# Efuse.net
KiCad netlist of a schematic drawn in Altium Designer
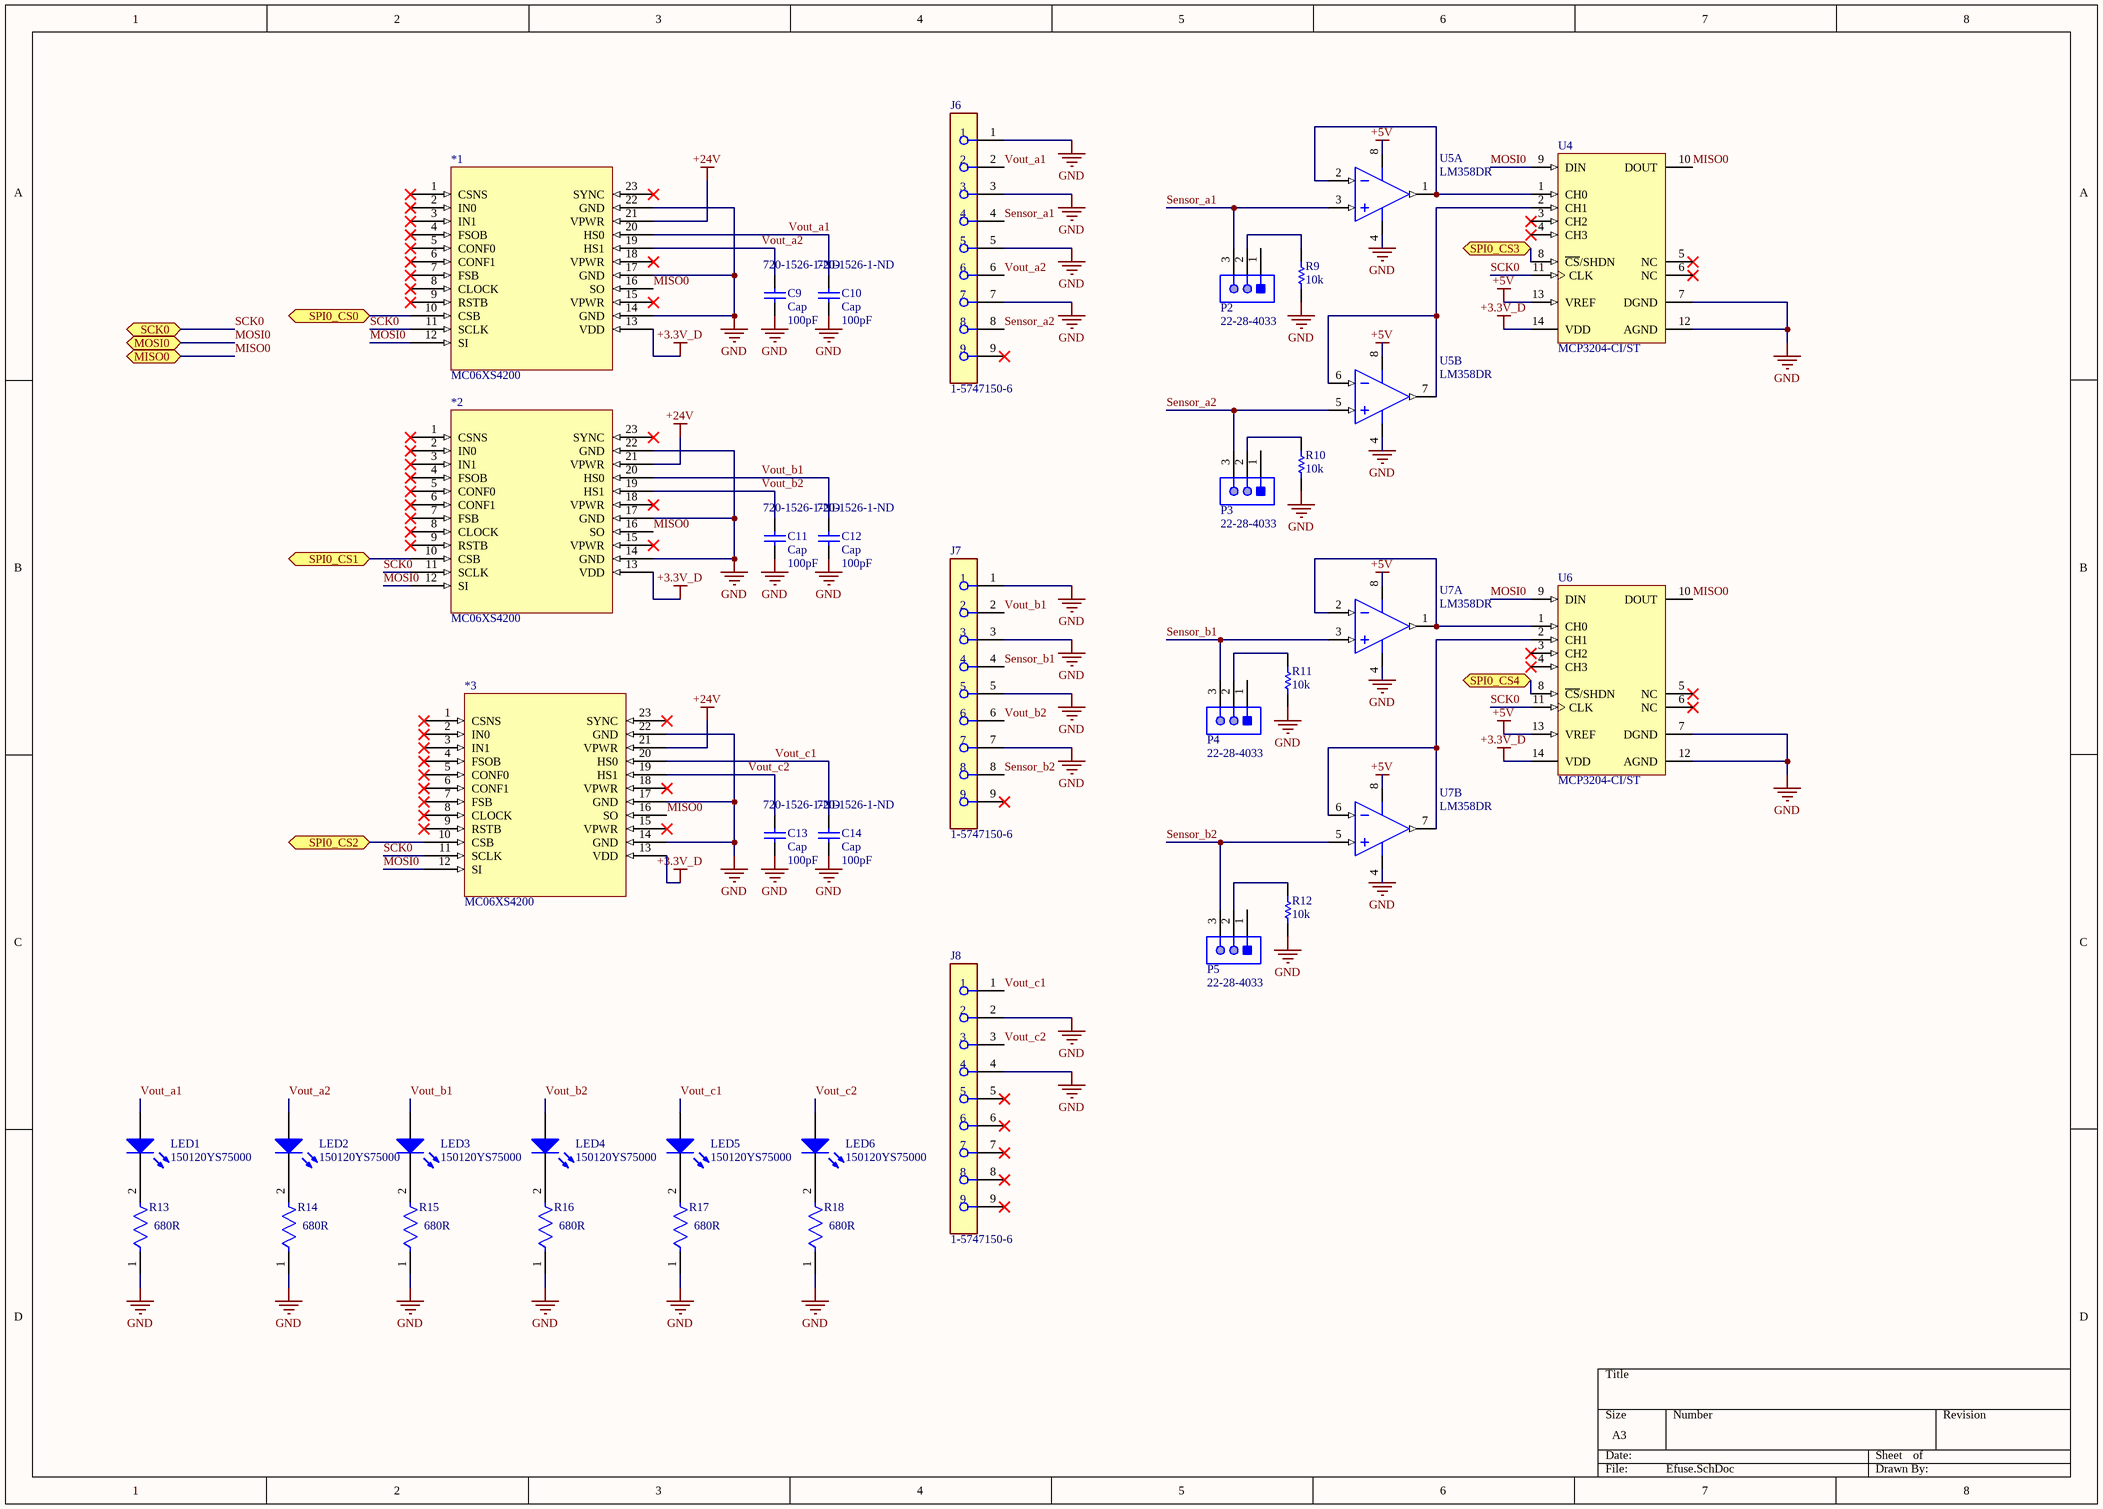
[diagram p0: Efuse.SchDoc]

(export (version "E")
  (design (tool "Eeschema 10.0.6"))
  (components
    (comp (ref "*1")
      (value "MC06XS4200")
      (footprint "MC06XS4200:PQFN50P1200X1200X220_HS-33N")
      (libsource (lib "MC06XS4200") (part "MC06XS4200"))
    )
    (comp (ref "*2")
      (value "MC06XS4200")
      (footprint "MC06XS4200:PQFN50P1200X1200X220_HS-33N")
      (libsource (lib "MC06XS4200") (part "MC06XS4200"))
    )
    (comp (ref "*3")
      (value "MC06XS4200")
      (footprint "MC06XS4200:PQFN50P1200X1200X220_HS-33N")
      (libsource (lib "MC06XS4200") (part "MC06XS4200"))
    )
    (comp (ref "C9")
      (value "Cap")
      (footprint "CAPC1608X95X40LL15T15")
      (description "MULTICOMP - MC0603F223Z500CT - KONDENSATOR, 0.022µF, 50V, Y5V, 0603")
      (fields
        (field (name "ALTIUM_VALUE") "100pF")
        (field (name "MANUFACTURER") "Multicomp")
        (field (name "MANUFACTURER PART NUMBER") "MC0603F223Z500CT")
        (field (name "SUPPLIER PART NUMBER 1") "720-1526-1-ND")
        (field (name "PUBLISHER") "Altium Limited")
      )
      (libsource (lib "Miscellaneous Devices") (part "Cap"))
    )
    (comp (ref "C10")
      (value "Cap")
      (footprint "CAPC1608X95X40LL15T15")
      (description "MULTICOMP - MC0603F223Z500CT - KONDENSATOR, 0.022µF, 50V, Y5V, 0603")
      (fields
        (field (name "ALTIUM_VALUE") "100pF")
        (field (name "MANUFACTURER") "Multicomp")
        (field (name "MANUFACTURER PART NUMBER") "MC0603F223Z500CT")
        (field (name "SUPPLIER PART NUMBER 1") "720-1526-1-ND")
        (field (name "PUBLISHER") "Altium Limited")
      )
      (libsource (lib "Miscellaneous Devices") (part "Cap"))
    )
    (comp (ref "C11")
      (value "Cap")
      (footprint "CAPC1608X95X40LL15T15")
      (description "MULTICOMP - MC0603F223Z500CT - KONDENSATOR, 0.022µF, 50V, Y5V, 0603")
      (fields
        (field (name "ALTIUM_VALUE") "100pF")
        (field (name "MANUFACTURER") "Multicomp")
        (field (name "MANUFACTURER PART NUMBER") "MC0603F223Z500CT")
        (field (name "SUPPLIER PART NUMBER 1") "720-1526-1-ND")
        (field (name "PUBLISHER") "Altium Limited")
      )
      (libsource (lib "Miscellaneous Devices") (part "Cap"))
    )
    (comp (ref "C12")
      (value "Cap")
      (footprint "CAPC1608X95X40LL15T15")
      (description "MULTICOMP - MC0603F223Z500CT - KONDENSATOR, 0.022µF, 50V, Y5V, 0603")
      (fields
        (field (name "ALTIUM_VALUE") "100pF")
        (field (name "MANUFACTURER") "Multicomp")
        (field (name "MANUFACTURER PART NUMBER") "MC0603F223Z500CT")
        (field (name "SUPPLIER PART NUMBER 1") "720-1526-1-ND")
        (field (name "PUBLISHER") "Altium Limited")
      )
      (libsource (lib "Miscellaneous Devices") (part "Cap"))
    )
    (comp (ref "C13")
      (value "Cap")
      (footprint "CAPC1608X95X40LL15T15")
      (description "MULTICOMP - MC0603F223Z500CT - KONDENSATOR, 0.022µF, 50V, Y5V, 0603")
      (fields
        (field (name "ALTIUM_VALUE") "100pF")
        (field (name "MANUFACTURER") "Multicomp")
        (field (name "MANUFACTURER PART NUMBER") "MC0603F223Z500CT")
        (field (name "SUPPLIER PART NUMBER 1") "720-1526-1-ND")
        (field (name "PUBLISHER") "Altium Limited")
      )
      (libsource (lib "Miscellaneous Devices") (part "Cap"))
    )
    (comp (ref "C14")
      (value "Cap")
      (footprint "CAPC1608X95X40LL15T15")
      (description "MULTICOMP - MC0603F223Z500CT - KONDENSATOR, 0.022µF, 50V, Y5V, 0603")
      (fields
        (field (name "ALTIUM_VALUE") "100pF")
        (field (name "MANUFACTURER") "Multicomp")
        (field (name "MANUFACTURER PART NUMBER") "MC0603F223Z500CT")
        (field (name "SUPPLIER PART NUMBER 1") "720-1526-1-ND")
        (field (name "PUBLISHER") "Altium Limited")
      )
      (libsource (lib "Miscellaneous Devices") (part "Cap"))
    )
    (comp (ref "J6")
      (value "1-5747150-6")
      (footprint "FP-1-5747150-6-MFG")
      (description "CONN D-SUB RCPT 9POS VERT SOLDER")
      (fields
        (field (name "OCTOPART") "https://octopart.com/1-5747150-6-te+connectivity-39500344")
        (field (name "MANUFACTURER") "TE Connectivity")
      )
      (libsource (lib "Altium Content Vault") (part "deee9d0d87fff07c08bdfa5b86cd5a5"))
    )
    (comp (ref "J7")
      (value "1-5747150-6")
      (footprint "FP-1-5747150-6-MFG")
      (description "CONN D-SUB RCPT 9POS VERT SOLDER")
      (fields
        (field (name "OCTOPART") "https://octopart.com/1-5747150-6-te+connectivity-39500344")
        (field (name "MANUFACTURER") "TE Connectivity")
      )
      (libsource (lib "Altium Content Vault") (part "deee9d0d87fff07c08bdfa5b86cd5a5"))
    )
    (comp (ref "J8")
      (value "1-5747150-6")
      (footprint "FP-1-5747150-6-MFG")
      (description "CONN D-SUB RCPT 9POS VERT SOLDER")
      (fields
        (field (name "OCTOPART") "https://octopart.com/1-5747150-6-te+connectivity-39500344")
        (field (name "MANUFACTURER") "TE Connectivity")
      )
      (libsource (lib "Altium Content Vault") (part "deee9d0d87fff07c08bdfa5b86cd5a5"))
    )
    (comp (ref "LED1")
      (value "150120YS75000")
      (footprint "1206_A")
      (description "SMD mono-color Chip LED, WL-SMCW, Yellow")
      (fields (field (name "MANUFACTURER") "Wuerth Elektronik"))
      (libsource (lib "Altium Content Vault") (part "WE-LED_K1A2-2"))
    )
    (comp (ref "LED2")
      (value "150120YS75000")
      (footprint "1206_A")
      (description "SMD mono-color Chip LED, WL-SMCW, Yellow")
      (fields (field (name "MANUFACTURER") "Wuerth Elektronik"))
      (libsource (lib "Altium Content Vault") (part "WE-LED_K1A2-2"))
    )
    (comp (ref "LED3")
      (value "150120YS75000")
      (footprint "1206_A")
      (description "SMD mono-color Chip LED, WL-SMCW, Yellow")
      (fields (field (name "MANUFACTURER") "Wuerth Elektronik"))
      (libsource (lib "Altium Content Vault") (part "WE-LED_K1A2-2"))
    )
    (comp (ref "LED4")
      (value "150120YS75000")
      (footprint "1206_A")
      (description "SMD mono-color Chip LED, WL-SMCW, Yellow")
      (fields (field (name "MANUFACTURER") "Wuerth Elektronik"))
      (libsource (lib "Altium Content Vault") (part "WE-LED_K1A2-2"))
    )
    (comp (ref "LED5")
      (value "150120YS75000")
      (footprint "1206_A")
      (description "SMD mono-color Chip LED, WL-SMCW, Yellow")
      (fields (field (name "MANUFACTURER") "Wuerth Elektronik"))
      (libsource (lib "Altium Content Vault") (part "WE-LED_K1A2-2"))
    )
    (comp (ref "LED6")
      (value "150120YS75000")
      (footprint "1206_A")
      (description "SMD mono-color Chip LED, WL-SMCW, Yellow")
      (fields (field (name "MANUFACTURER") "Wuerth Elektronik"))
      (libsource (lib "Altium Content Vault") (part "WE-LED_K1A2-2"))
    )
    (comp (ref "P2")
      (value "22-28-4033")
      (footprint "MOLX-22-28-4033_V")
      (description "Male Header, Pitch 2.54 mm, 1 x 3 Position, Height 8.38 mm, Tail Length 3.18 mm, RoHS, Bulk")
      (fields (field (name "MANUFACTURER") "Molex"))
      (libsource (lib "Altium Content Vault") (part "CN-1P-M-R3"))
    )
    (comp (ref "P3")
      (value "22-28-4033")
      (footprint "MOLX-22-28-4033_V")
      (description "Male Header, Pitch 2.54 mm, 1 x 3 Position, Height 8.38 mm, Tail Length 3.18 mm, RoHS, Bulk")
      (fields (field (name "MANUFACTURER") "Molex"))
      (libsource (lib "Altium Content Vault") (part "CN-1P-M-R3"))
    )
    (comp (ref "P4")
      (value "22-28-4033")
      (footprint "MOLX-22-28-4033_V")
      (description "Male Header, Pitch 2.54 mm, 1 x 3 Position, Height 8.38 mm, Tail Length 3.18 mm, RoHS, Bulk")
      (fields (field (name "MANUFACTURER") "Molex"))
      (libsource (lib "Altium Content Vault") (part "CN-1P-M-R3"))
    )
    (comp (ref "P5")
      (value "22-28-4033")
      (footprint "MOLX-22-28-4033_V")
      (description "Male Header, Pitch 2.54 mm, 1 x 3 Position, Height 8.38 mm, Tail Length 3.18 mm, RoHS, Bulk")
      (fields (field (name "MANUFACTURER") "Molex"))
      (libsource (lib "Altium Content Vault") (part "CN-1P-M-R3"))
    )
    (comp (ref "R9")
      (value "10k")
      (footprint "RESC1005X40X25NL05T05")
      (fields (field (name "PART NUMBER") "ERT-J0ER103J") (field (name "MANUFACTURER") "Panasonic"))
      (libsource (lib "Altium Content Vault") (part "RES"))
    )
    (comp (ref "R10")
      (value "10k")
      (footprint "RESC1005X40X25NL05T05")
      (fields (field (name "PART NUMBER") "ERT-J0ER103J") (field (name "MANUFACTURER") "Panasonic"))
      (libsource (lib "Altium Content Vault") (part "RES"))
    )
    (comp (ref "R11")
      (value "10k")
      (footprint "RESC1005X40X25NL05T05")
      (fields (field (name "PART NUMBER") "ERT-J0ER103J") (field (name "MANUFACTURER") "Panasonic"))
      (libsource (lib "Altium Content Vault") (part "RES"))
    )
    (comp (ref "R12")
      (value "10k")
      (footprint "RESC1005X40X25NL05T05")
      (fields (field (name "PART NUMBER") "ERT-J0ER103J") (field (name "MANUFACTURER") "Panasonic"))
      (libsource (lib "Altium Content Vault") (part "RES"))
    )
    (comp (ref "R13")
      (value "CRCW0603680RFKEA")
      (footprint "FP-CRCW0603-e3-MFG")
      (description "RES Thick Film, 680Ω, 1%, 0.1W, 100ppm/°C, 0603")
      (fields (field (name "TOLERANCE") "1%") (field (name "RESISTANCE") "680R"))
      (libsource (lib "Altium Content Vault") (part "1029c3af85768c4190bb7ad29bc67b5"))
    )
    (comp (ref "R14")
      (value "CRCW0603680RFKEA")
      (footprint "FP-CRCW0603-e3-MFG")
      (description "RES Thick Film, 680Ω, 1%, 0.1W, 100ppm/°C, 0603")
      (fields (field (name "TOLERANCE") "1%") (field (name "RESISTANCE") "680R"))
      (libsource (lib "Altium Content Vault") (part "1029c3af85768c4190bb7ad29bc67b5"))
    )
    (comp (ref "R15")
      (value "CRCW0603680RFKEA")
      (footprint "FP-CRCW0603-e3-MFG")
      (description "RES Thick Film, 680Ω, 1%, 0.1W, 100ppm/°C, 0603")
      (fields (field (name "TOLERANCE") "1%") (field (name "RESISTANCE") "680R"))
      (libsource (lib "Altium Content Vault") (part "1029c3af85768c4190bb7ad29bc67b5"))
    )
    (comp (ref "R16")
      (value "CRCW0603680RFKEA")
      (footprint "FP-CRCW0603-e3-MFG")
      (description "RES Thick Film, 680Ω, 1%, 0.1W, 100ppm/°C, 0603")
      (fields (field (name "TOLERANCE") "1%") (field (name "RESISTANCE") "680R"))
      (libsource (lib "Altium Content Vault") (part "1029c3af85768c4190bb7ad29bc67b5"))
    )
    (comp (ref "R17")
      (value "CRCW0603680RFKEA")
      (footprint "FP-CRCW0603-e3-MFG")
      (description "RES Thick Film, 680Ω, 1%, 0.1W, 100ppm/°C, 0603")
      (fields (field (name "TOLERANCE") "1%") (field (name "RESISTANCE") "680R"))
      (libsource (lib "Altium Content Vault") (part "1029c3af85768c4190bb7ad29bc67b5"))
    )
    (comp (ref "R18")
      (value "CRCW0603680RFKEA")
      (footprint "FP-CRCW0603-e3-MFG")
      (description "RES Thick Film, 680Ω, 1%, 0.1W, 100ppm/°C, 0603")
      (fields (field (name "TOLERANCE") "1%") (field (name "RESISTANCE") "680R"))
      (libsource (lib "Altium Content Vault") (part "1029c3af85768c4190bb7ad29bc67b5"))
    )
    (comp (ref "U4")
      (value "MCP3204-CI/ST")
      (footprint "TSSOP-ST14_N")
      (libsource (lib "Altium Content Vault") (part "CON-ADC-MCP3004-14"))
    )
    (comp (ref "U5")
      (value "LM358DR")
      (footprint "D0008A_L")
      (libsource (lib "Altium Content Vault") (part "TI-LM358-8"))
    )
    (comp (ref "U6")
      (value "MCP3204-CI/ST")
      (footprint "TSSOP-ST14_N")
      (libsource (lib "Altium Content Vault") (part "CON-ADC-MCP3004-14"))
    )
    (comp (ref "U7")
      (value "LM358DR")
      (footprint "D0008A_L")
      (libsource (lib "Altium Content Vault") (part "TI-LM358-8"))
    )
  )
  (nets
    (net (code "1") (name "+3.3V_D") (class "Default")
      (node (ref "*1") (pin "13") (pinfunction "VDD_13") (pintype "input"))
      (node (ref "*2") (pin "13") (pinfunction "VDD_13") (pintype "input"))
      (node (ref "*3") (pin "13") (pinfunction "VDD_13") (pintype "input"))
      (node (ref "U4") (pin "14") (pinfunction "VDD_14") (pintype "power_in"))
      (node (ref "U6") (pin "14") (pinfunction "VDD_14") (pintype "power_in"))
    )
    (net (code "2") (name "+5V") (class "Default")
      (node (ref "U4") (pin "13") (pinfunction "VREF_13") (pintype "input"))
      (node (ref "U5") (pin "8") (pinfunction "VCC_8") (pintype "power_in"))
      (node (ref "U6") (pin "13") (pinfunction "VREF_13") (pintype "input"))
      (node (ref "U7") (pin "8") (pinfunction "VCC_8") (pintype "power_in"))
    )
    (net (code "3") (name "+24V") (class "Default")
      (node (ref "*1") (pin "21") (pinfunction "VPWR_21") (pintype "input"))
      (node (ref "*2") (pin "21") (pinfunction "VPWR_21") (pintype "input"))
      (node (ref "*3") (pin "21") (pinfunction "VPWR_21") (pintype "input"))
    )
    (net (code "4") (name "/MISO0") (class "Default")
      (node (ref "*1") (pin "16") (pinfunction "SO_16") (pintype "input"))
      (node (ref "*2") (pin "16") (pinfunction "SO_16") (pintype "input"))
      (node (ref "*3") (pin "16") (pinfunction "SO_16") (pintype "input"))
      (node (ref "U4") (pin "10") (pinfunction "DOUT_10") (pintype "tri_state"))
      (node (ref "U6") (pin "10") (pinfunction "DOUT_10") (pintype "tri_state"))
    )
    (net (code "5") (name "/MOSI0") (class "Default")
      (node (ref "*1") (pin "12") (pinfunction "SI_12") (pintype "input"))
      (node (ref "*2") (pin "12") (pinfunction "SI_12") (pintype "input"))
      (node (ref "*3") (pin "12") (pinfunction "SI_12") (pintype "input"))
      (node (ref "U4") (pin "9") (pinfunction "DIN_9") (pintype "input"))
      (node (ref "U6") (pin "9") (pinfunction "DIN_9") (pintype "input"))
    )
    (net (code "6") (name "/SCK0") (class "Default")
      (node (ref "*1") (pin "11") (pinfunction "SCLK_11") (pintype "input"))
      (node (ref "*2") (pin "11") (pinfunction "SCLK_11") (pintype "input"))
      (node (ref "*3") (pin "11") (pinfunction "SCLK_11") (pintype "input"))
      (node (ref "U4") (pin "11") (pinfunction "CLK_11") (pintype "input"))
      (node (ref "U6") (pin "11") (pinfunction "CLK_11") (pintype "input"))
    )
    (net (code "7") (name "/SPI0_CS0") (class "Default")
      (node (ref "*1") (pin "10") (pinfunction "CSB_10") (pintype "input"))
    )
    (net (code "8") (name "/SPI0_CS1") (class "Default")
      (node (ref "*2") (pin "10") (pinfunction "CSB_10") (pintype "input"))
    )
    (net (code "9") (name "/SPI0_CS2") (class "Default")
      (node (ref "*3") (pin "10") (pinfunction "CSB_10") (pintype "input"))
    )
    (net (code "10") (name "/SPI0_CS3") (class "Default")
      (node (ref "U4") (pin "8") (pinfunction "~{CS}/SHDN_8") (pintype "input"))
    )
    (net (code "11") (name "/SPI0_CS4") (class "Default")
      (node (ref "U6") (pin "8") (pinfunction "~{CS}/SHDN_8") (pintype "input"))
    )
    (net (code "12") (name "/Sensor_a1") (class "Default")
      (node (ref "J6") (pin "4") (pinfunction "4_4") (pintype "passive"))
      (node (ref "P2") (pin "3") (pinfunction "3_3") (pintype "passive"))
      (node (ref "U5") (pin "3") (pinfunction "1IN+_3") (pintype "input"))
    )
    (net (code "13") (name "/Sensor_a2") (class "Default")
      (node (ref "J6") (pin "8") (pinfunction "8_8") (pintype "passive"))
      (node (ref "P3") (pin "3") (pinfunction "3_3") (pintype "passive"))
      (node (ref "U5") (pin "5") (pinfunction "2IN+_5") (pintype "input"))
    )
    (net (code "14") (name "/Sensor_b1") (class "Default")
      (node (ref "J7") (pin "4") (pinfunction "4_4") (pintype "passive"))
      (node (ref "P4") (pin "3") (pinfunction "3_3") (pintype "passive"))
      (node (ref "U7") (pin "3") (pinfunction "1IN+_3") (pintype "input"))
    )
    (net (code "15") (name "/Sensor_b2") (class "Default")
      (node (ref "J7") (pin "8") (pinfunction "8_8") (pintype "passive"))
      (node (ref "P5") (pin "3") (pinfunction "3_3") (pintype "passive"))
      (node (ref "U7") (pin "5") (pinfunction "2IN+_5") (pintype "input"))
    )
    (net (code "16") (name "/Vout_a1") (class "Default")
      (node (ref "*1") (pin "20") (pinfunction "HS0_20") (pintype "input"))
      (node (ref "C10") (pin "2") (pinfunction "2_2") (pintype "passive"))
      (node (ref "J6") (pin "2") (pinfunction "2_2") (pintype "passive"))
      (node (ref "LED1") (pin "2") (pinfunction "A_2") (pintype "passive"))
    )
    (net (code "17") (name "/Vout_a2") (class "Default")
      (node (ref "*1") (pin "19") (pinfunction "HS1_19") (pintype "input"))
      (node (ref "C9") (pin "2") (pinfunction "2_2") (pintype "passive"))
      (node (ref "J6") (pin "6") (pinfunction "6_6") (pintype "passive"))
      (node (ref "LED2") (pin "2") (pinfunction "A_2") (pintype "passive"))
    )
    (net (code "18") (name "/Vout_b1") (class "Default")
      (node (ref "*2") (pin "20") (pinfunction "HS0_20") (pintype "input"))
      (node (ref "C12") (pin "2") (pinfunction "2_2") (pintype "passive"))
      (node (ref "J7") (pin "2") (pinfunction "2_2") (pintype "passive"))
      (node (ref "LED3") (pin "2") (pinfunction "A_2") (pintype "passive"))
    )
    (net (code "19") (name "/Vout_b2") (class "Default")
      (node (ref "*2") (pin "19") (pinfunction "HS1_19") (pintype "input"))
      (node (ref "C11") (pin "2") (pinfunction "2_2") (pintype "passive"))
      (node (ref "J7") (pin "6") (pinfunction "6_6") (pintype "passive"))
      (node (ref "LED4") (pin "2") (pinfunction "A_2") (pintype "passive"))
    )
    (net (code "20") (name "/Vout_c1") (class "Default")
      (node (ref "*3") (pin "20") (pinfunction "HS0_20") (pintype "input"))
      (node (ref "C14") (pin "2") (pinfunction "2_2") (pintype "passive"))
      (node (ref "J8") (pin "1") (pinfunction "1_1") (pintype "passive"))
      (node (ref "LED5") (pin "2") (pinfunction "A_2") (pintype "passive"))
    )
    (net (code "21") (name "/Vout_c2") (class "Default")
      (node (ref "*3") (pin "19") (pinfunction "HS1_19") (pintype "input"))
      (node (ref "C13") (pin "2") (pinfunction "2_2") (pintype "passive"))
      (node (ref "J8") (pin "3") (pinfunction "3_3") (pintype "passive"))
      (node (ref "LED6") (pin "2") (pinfunction "A_2") (pintype "passive"))
    )
    (net (code "22") (name "GND") (class "Default")
      (node (ref "*1") (pin "14") (pinfunction "GND_14") (pintype "input"))
      (node (ref "*1") (pin "17") (pinfunction "GND_17") (pintype "input"))
      (node (ref "*1") (pin "22") (pinfunction "GND_22") (pintype "input"))
      (node (ref "*2") (pin "14") (pinfunction "GND_14") (pintype "input"))
      (node (ref "*2") (pin "17") (pinfunction "GND_17") (pintype "input"))
      (node (ref "*2") (pin "22") (pinfunction "GND_22") (pintype "input"))
      (node (ref "*3") (pin "14") (pinfunction "GND_14") (pintype "input"))
      (node (ref "*3") (pin "17") (pinfunction "GND_17") (pintype "input"))
      (node (ref "*3") (pin "22") (pinfunction "GND_22") (pintype "input"))
      (node (ref "C10") (pin "1") (pinfunction "1_1") (pintype "passive"))
      (node (ref "C11") (pin "1") (pinfunction "1_1") (pintype "passive"))
      (node (ref "C12") (pin "1") (pinfunction "1_1") (pintype "passive"))
      (node (ref "C13") (pin "1") (pinfunction "1_1") (pintype "passive"))
      (node (ref "C14") (pin "1") (pinfunction "1_1") (pintype "passive"))
      (node (ref "C9") (pin "1") (pinfunction "1_1") (pintype "passive"))
      (node (ref "J6") (pin "1") (pinfunction "1_1") (pintype "passive"))
      (node (ref "J6") (pin "3") (pinfunction "3_3") (pintype "passive"))
      (node (ref "J6") (pin "5") (pinfunction "5_5") (pintype "passive"))
      (node (ref "J6") (pin "7") (pinfunction "7_7") (pintype "passive"))
      (node (ref "J7") (pin "1") (pinfunction "1_1") (pintype "passive"))
      (node (ref "J7") (pin "3") (pinfunction "3_3") (pintype "passive"))
      (node (ref "J7") (pin "5") (pinfunction "5_5") (pintype "passive"))
      (node (ref "J7") (pin "7") (pinfunction "7_7") (pintype "passive"))
      (node (ref "J8") (pin "2") (pinfunction "2_2") (pintype "passive"))
      (node (ref "J8") (pin "4") (pinfunction "4_4") (pintype "passive"))
      (node (ref "R10") (pin "1") (pinfunction "1_1") (pintype "passive"))
      (node (ref "R11") (pin "1") (pinfunction "1_1") (pintype "passive"))
      (node (ref "R12") (pin "1") (pinfunction "1_1") (pintype "passive"))
      (node (ref "R13") (pin "1") (pinfunction "1_1") (pintype "passive"))
      (node (ref "R14") (pin "1") (pinfunction "1_1") (pintype "passive"))
      (node (ref "R15") (pin "1") (pinfunction "1_1") (pintype "passive"))
      (node (ref "R16") (pin "1") (pinfunction "1_1") (pintype "passive"))
      (node (ref "R17") (pin "1") (pinfunction "1_1") (pintype "passive"))
      (node (ref "R18") (pin "1") (pinfunction "1_1") (pintype "passive"))
      (node (ref "R9") (pin "1") (pinfunction "1_1") (pintype "passive"))
      (node (ref "U4") (pin "12") (pinfunction "AGND_12") (pintype "power_in"))
      (node (ref "U4") (pin "7") (pinfunction "DGND_7") (pintype "power_in"))
      (node (ref "U5") (pin "4") (pinfunction "GND_4") (pintype "power_in"))
      (node (ref "U6") (pin "12") (pinfunction "AGND_12") (pintype "power_in"))
      (node (ref "U6") (pin "7") (pinfunction "DGND_7") (pintype "power_in"))
      (node (ref "U7") (pin "4") (pinfunction "GND_4") (pintype "power_in"))
    )
    (net (code "23") (name "Net-(LED1-K)") (class "Default")
      (node (ref "LED1") (pin "1") (pinfunction "K_1") (pintype "passive"))
      (node (ref "R13") (pin "2") (pinfunction "2_2") (pintype "passive"))
    )
    (net (code "24") (name "Net-(LED2-K)") (class "Default")
      (node (ref "LED2") (pin "1") (pinfunction "K_1") (pintype "passive"))
      (node (ref "R14") (pin "2") (pinfunction "2_2") (pintype "passive"))
    )
    (net (code "25") (name "Net-(LED3-K)") (class "Default")
      (node (ref "LED3") (pin "1") (pinfunction "K_1") (pintype "passive"))
      (node (ref "R15") (pin "2") (pinfunction "2_2") (pintype "passive"))
    )
    (net (code "26") (name "Net-(LED4-K)") (class "Default")
      (node (ref "LED4") (pin "1") (pinfunction "K_1") (pintype "passive"))
      (node (ref "R16") (pin "2") (pinfunction "2_2") (pintype "passive"))
    )
    (net (code "27") (name "Net-(LED5-K)") (class "Default")
      (node (ref "LED5") (pin "1") (pinfunction "K_1") (pintype "passive"))
      (node (ref "R17") (pin "2") (pinfunction "2_2") (pintype "passive"))
    )
    (net (code "28") (name "Net-(LED6-K)") (class "Default")
      (node (ref "LED6") (pin "1") (pinfunction "K_1") (pintype "passive"))
      (node (ref "R18") (pin "2") (pinfunction "2_2") (pintype "passive"))
    )
    (net (code "29") (name "Net-(P2-Pad2)") (class "Default")
      (node (ref "P2") (pin "2") (pinfunction "2_2") (pintype "passive"))
      (node (ref "R9") (pin "2") (pinfunction "2_2") (pintype "passive"))
    )
    (net (code "30") (name "Net-(P3-Pad2)") (class "Default")
      (node (ref "P3") (pin "2") (pinfunction "2_2") (pintype "passive"))
      (node (ref "R10") (pin "2") (pinfunction "2_2") (pintype "passive"))
    )
    (net (code "31") (name "Net-(P4-Pad2)") (class "Default")
      (node (ref "P4") (pin "2") (pinfunction "2_2") (pintype "passive"))
      (node (ref "R11") (pin "2") (pinfunction "2_2") (pintype "passive"))
    )
    (net (code "32") (name "Net-(P5-Pad2)") (class "Default")
      (node (ref "P5") (pin "2") (pinfunction "2_2") (pintype "passive"))
      (node (ref "R12") (pin "2") (pinfunction "2_2") (pintype "passive"))
    )
    (net (code "33") (name "Net-(U4-CH0)") (class "Default")
      (node (ref "U4") (pin "1") (pinfunction "CH0_1") (pintype "input"))
      (node (ref "U5") (pin "1") (pinfunction "1OUT_1") (pintype "output"))
      (node (ref "U5") (pin "2") (pinfunction "1IN-_2") (pintype "input"))
    )
    (net (code "34") (name "Net-(U4-CH1)") (class "Default")
      (node (ref "U4") (pin "2") (pinfunction "CH1_2") (pintype "input"))
      (node (ref "U5") (pin "6") (pinfunction "2IN-_6") (pintype "input"))
      (node (ref "U5") (pin "7") (pinfunction "2OUT_7") (pintype "output"))
    )
    (net (code "35") (name "Net-(U6-CH0)") (class "Default")
      (node (ref "U6") (pin "1") (pinfunction "CH0_1") (pintype "input"))
      (node (ref "U7") (pin "1") (pinfunction "1OUT_1") (pintype "output"))
      (node (ref "U7") (pin "2") (pinfunction "1IN-_2") (pintype "input"))
    )
    (net (code "36") (name "Net-(U6-CH1)") (class "Default")
      (node (ref "U6") (pin "2") (pinfunction "CH1_2") (pintype "input"))
      (node (ref "U7") (pin "6") (pinfunction "2IN-_6") (pintype "input"))
      (node (ref "U7") (pin "7") (pinfunction "2OUT_7") (pintype "output"))
    )
    (net (code "37") (name "unconnected-(*1-CLOCK-Pad8)") (class "Default")
      (node (ref "*1") (pin "8") (pinfunction "CLOCK_8") (pintype "input+no_connect"))
    )
    (net (code "38") (name "unconnected-(*1-CONF0-Pad5)") (class "Default")
      (node (ref "*1") (pin "5") (pinfunction "CONF0_5") (pintype "input+no_connect"))
    )
    (net (code "39") (name "unconnected-(*1-CONF1-Pad6)") (class "Default")
      (node (ref "*1") (pin "6") (pinfunction "CONF1_6") (pintype "input+no_connect"))
    )
    (net (code "40") (name "unconnected-(*1-CSNS-Pad1)") (class "Default")
      (node (ref "*1") (pin "1") (pinfunction "CSNS_1") (pintype "input+no_connect"))
    )
    (net (code "41") (name "unconnected-(*1-FSB-Pad7)") (class "Default")
      (node (ref "*1") (pin "7") (pinfunction "FSB_7") (pintype "input+no_connect"))
    )
    (net (code "42") (name "unconnected-(*1-FSOB-Pad4)") (class "Default")
      (node (ref "*1") (pin "4") (pinfunction "FSOB_4") (pintype "input+no_connect"))
    )
    (net (code "43") (name "unconnected-(*1-IN0-Pad2)") (class "Default")
      (node (ref "*1") (pin "2") (pinfunction "IN0_2") (pintype "input+no_connect"))
    )
    (net (code "44") (name "unconnected-(*1-IN1-Pad3)") (class "Default")
      (node (ref "*1") (pin "3") (pinfunction "IN1_3") (pintype "input+no_connect"))
    )
    (net (code "45") (name "unconnected-(*1-RSTB-Pad9)") (class "Default")
      (node (ref "*1") (pin "9") (pinfunction "RSTB_9") (pintype "input+no_connect"))
    )
    (net (code "46") (name "unconnected-(*1-SYNC-Pad23)") (class "Default")
      (node (ref "*1") (pin "23") (pinfunction "SYNC_23") (pintype "input+no_connect"))
    )
    (net (code "47") (name "unconnected-(*1-VPWR-Pad15)") (class "Default")
      (node (ref "*1") (pin "15") (pinfunction "VPWR_15") (pintype "input+no_connect"))
    )
    (net (code "48") (name "unconnected-(*1-VPWR-Pad18)") (class "Default")
      (node (ref "*1") (pin "18") (pinfunction "VPWR_18") (pintype "input+no_connect"))
    )
    (net (code "49") (name "unconnected-(*2-CLOCK-Pad8)") (class "Default")
      (node (ref "*2") (pin "8") (pinfunction "CLOCK_8") (pintype "input+no_connect"))
    )
    (net (code "50") (name "unconnected-(*2-CONF0-Pad5)") (class "Default")
      (node (ref "*2") (pin "5") (pinfunction "CONF0_5") (pintype "input+no_connect"))
    )
    (net (code "51") (name "unconnected-(*2-CONF1-Pad6)") (class "Default")
      (node (ref "*2") (pin "6") (pinfunction "CONF1_6") (pintype "input+no_connect"))
    )
    (net (code "52") (name "unconnected-(*2-CSNS-Pad1)") (class "Default")
      (node (ref "*2") (pin "1") (pinfunction "CSNS_1") (pintype "input+no_connect"))
    )
    (net (code "53") (name "unconnected-(*2-FSB-Pad7)") (class "Default")
      (node (ref "*2") (pin "7") (pinfunction "FSB_7") (pintype "input+no_connect"))
    )
    (net (code "54") (name "unconnected-(*2-FSOB-Pad4)") (class "Default")
      (node (ref "*2") (pin "4") (pinfunction "FSOB_4") (pintype "input+no_connect"))
    )
    (net (code "55") (name "unconnected-(*2-IN0-Pad2)") (class "Default")
      (node (ref "*2") (pin "2") (pinfunction "IN0_2") (pintype "input+no_connect"))
    )
    (net (code "56") (name "unconnected-(*2-IN1-Pad3)") (class "Default")
      (node (ref "*2") (pin "3") (pinfunction "IN1_3") (pintype "input+no_connect"))
    )
    (net (code "57") (name "unconnected-(*2-RSTB-Pad9)") (class "Default")
      (node (ref "*2") (pin "9") (pinfunction "RSTB_9") (pintype "input+no_connect"))
    )
    (net (code "58") (name "unconnected-(*2-SYNC-Pad23)") (class "Default")
      (node (ref "*2") (pin "23") (pinfunction "SYNC_23") (pintype "input+no_connect"))
    )
    (net (code "59") (name "unconnected-(*2-VPWR-Pad15)") (class "Default")
      (node (ref "*2") (pin "15") (pinfunction "VPWR_15") (pintype "input+no_connect"))
    )
    (net (code "60") (name "unconnected-(*2-VPWR-Pad18)") (class "Default")
      (node (ref "*2") (pin "18") (pinfunction "VPWR_18") (pintype "input+no_connect"))
    )
    (net (code "61") (name "unconnected-(*3-CLOCK-Pad8)") (class "Default")
      (node (ref "*3") (pin "8") (pinfunction "CLOCK_8") (pintype "input+no_connect"))
    )
    (net (code "62") (name "unconnected-(*3-CONF0-Pad5)") (class "Default")
      (node (ref "*3") (pin "5") (pinfunction "CONF0_5") (pintype "input+no_connect"))
    )
    (net (code "63") (name "unconnected-(*3-CONF1-Pad6)") (class "Default")
      (node (ref "*3") (pin "6") (pinfunction "CONF1_6") (pintype "input+no_connect"))
    )
    (net (code "64") (name "unconnected-(*3-CSNS-Pad1)") (class "Default")
      (node (ref "*3") (pin "1") (pinfunction "CSNS_1") (pintype "input+no_connect"))
    )
    (net (code "65") (name "unconnected-(*3-FSB-Pad7)") (class "Default")
      (node (ref "*3") (pin "7") (pinfunction "FSB_7") (pintype "input+no_connect"))
    )
    (net (code "66") (name "unconnected-(*3-FSOB-Pad4)") (class "Default")
      (node (ref "*3") (pin "4") (pinfunction "FSOB_4") (pintype "input+no_connect"))
    )
    (net (code "67") (name "unconnected-(*3-IN0-Pad2)") (class "Default")
      (node (ref "*3") (pin "2") (pinfunction "IN0_2") (pintype "input+no_connect"))
    )
    (net (code "68") (name "unconnected-(*3-IN1-Pad3)") (class "Default")
      (node (ref "*3") (pin "3") (pinfunction "IN1_3") (pintype "input+no_connect"))
    )
    (net (code "69") (name "unconnected-(*3-RSTB-Pad9)") (class "Default")
      (node (ref "*3") (pin "9") (pinfunction "RSTB_9") (pintype "input+no_connect"))
    )
    (net (code "70") (name "unconnected-(*3-SYNC-Pad23)") (class "Default")
      (node (ref "*3") (pin "23") (pinfunction "SYNC_23") (pintype "input+no_connect"))
    )
    (net (code "71") (name "unconnected-(*3-VPWR-Pad15)") (class "Default")
      (node (ref "*3") (pin "15") (pinfunction "VPWR_15") (pintype "input+no_connect"))
    )
    (net (code "72") (name "unconnected-(*3-VPWR-Pad18)") (class "Default")
      (node (ref "*3") (pin "18") (pinfunction "VPWR_18") (pintype "input+no_connect"))
    )
    (net (code "73") (name "unconnected-(J6-Pad9)") (class "Default")
      (node (ref "J6") (pin "9") (pinfunction "9_9") (pintype "passive+no_connect"))
    )
    (net (code "74") (name "unconnected-(J7-Pad9)") (class "Default")
      (node (ref "J7") (pin "9") (pinfunction "9_9") (pintype "passive+no_connect"))
    )
    (net (code "75") (name "unconnected-(J8-Pad5)") (class "Default")
      (node (ref "J8") (pin "5") (pinfunction "5_5") (pintype "passive+no_connect"))
    )
    (net (code "76") (name "unconnected-(J8-Pad6)") (class "Default")
      (node (ref "J8") (pin "6") (pinfunction "6_6") (pintype "passive+no_connect"))
    )
    (net (code "77") (name "unconnected-(J8-Pad7)") (class "Default")
      (node (ref "J8") (pin "7") (pinfunction "7_7") (pintype "passive+no_connect"))
    )
    (net (code "78") (name "unconnected-(J8-Pad8)") (class "Default")
      (node (ref "J8") (pin "8") (pinfunction "8_8") (pintype "passive+no_connect"))
    )
    (net (code "79") (name "unconnected-(J8-Pad9)") (class "Default")
      (node (ref "J8") (pin "9") (pinfunction "9_9") (pintype "passive+no_connect"))
    )
    (net (code "80") (name "unconnected-(P2-Pad1)") (class "Default")
      (node (ref "P2") (pin "1") (pinfunction "1_1") (pintype "passive"))
    )
    (net (code "81") (name "unconnected-(P3-Pad1)") (class "Default")
      (node (ref "P3") (pin "1") (pinfunction "1_1") (pintype "passive"))
    )
    (net (code "82") (name "unconnected-(P4-Pad1)") (class "Default")
      (node (ref "P4") (pin "1") (pinfunction "1_1") (pintype "passive"))
    )
    (net (code "83") (name "unconnected-(P5-Pad1)") (class "Default")
      (node (ref "P5") (pin "1") (pinfunction "1_1") (pintype "passive"))
    )
    (net (code "84") (name "unconnected-(U4-CH2-Pad3)") (class "Default")
      (node (ref "U4") (pin "3") (pinfunction "CH2_3") (pintype "input+no_connect"))
    )
    (net (code "85") (name "unconnected-(U4-CH3-Pad4)") (class "Default")
      (node (ref "U4") (pin "4") (pinfunction "CH3_4") (pintype "input+no_connect"))
    )
    (net (code "86") (name "unconnected-(U4-NC-Pad5)") (class "Default")
      (node (ref "U4") (pin "5") (pinfunction "NC_5") (pintype "passive+no_connect"))
    )
    (net (code "87") (name "unconnected-(U4-NC-Pad6)") (class "Default")
      (node (ref "U4") (pin "6") (pinfunction "NC_6") (pintype "passive+no_connect"))
    )
    (net (code "88") (name "unconnected-(U6-CH2-Pad3)") (class "Default")
      (node (ref "U6") (pin "3") (pinfunction "CH2_3") (pintype "input+no_connect"))
    )
    (net (code "89") (name "unconnected-(U6-CH3-Pad4)") (class "Default")
      (node (ref "U6") (pin "4") (pinfunction "CH3_4") (pintype "input+no_connect"))
    )
    (net (code "90") (name "unconnected-(U6-NC-Pad5)") (class "Default")
      (node (ref "U6") (pin "5") (pinfunction "NC_5") (pintype "passive+no_connect"))
    )
    (net (code "91") (name "unconnected-(U6-NC-Pad6)") (class "Default")
      (node (ref "U6") (pin "6") (pinfunction "NC_6") (pintype "passive+no_connect"))
    )
  )
)
